# DumbCar.net
KiCad netlist of a schematic drawn in EAGLE
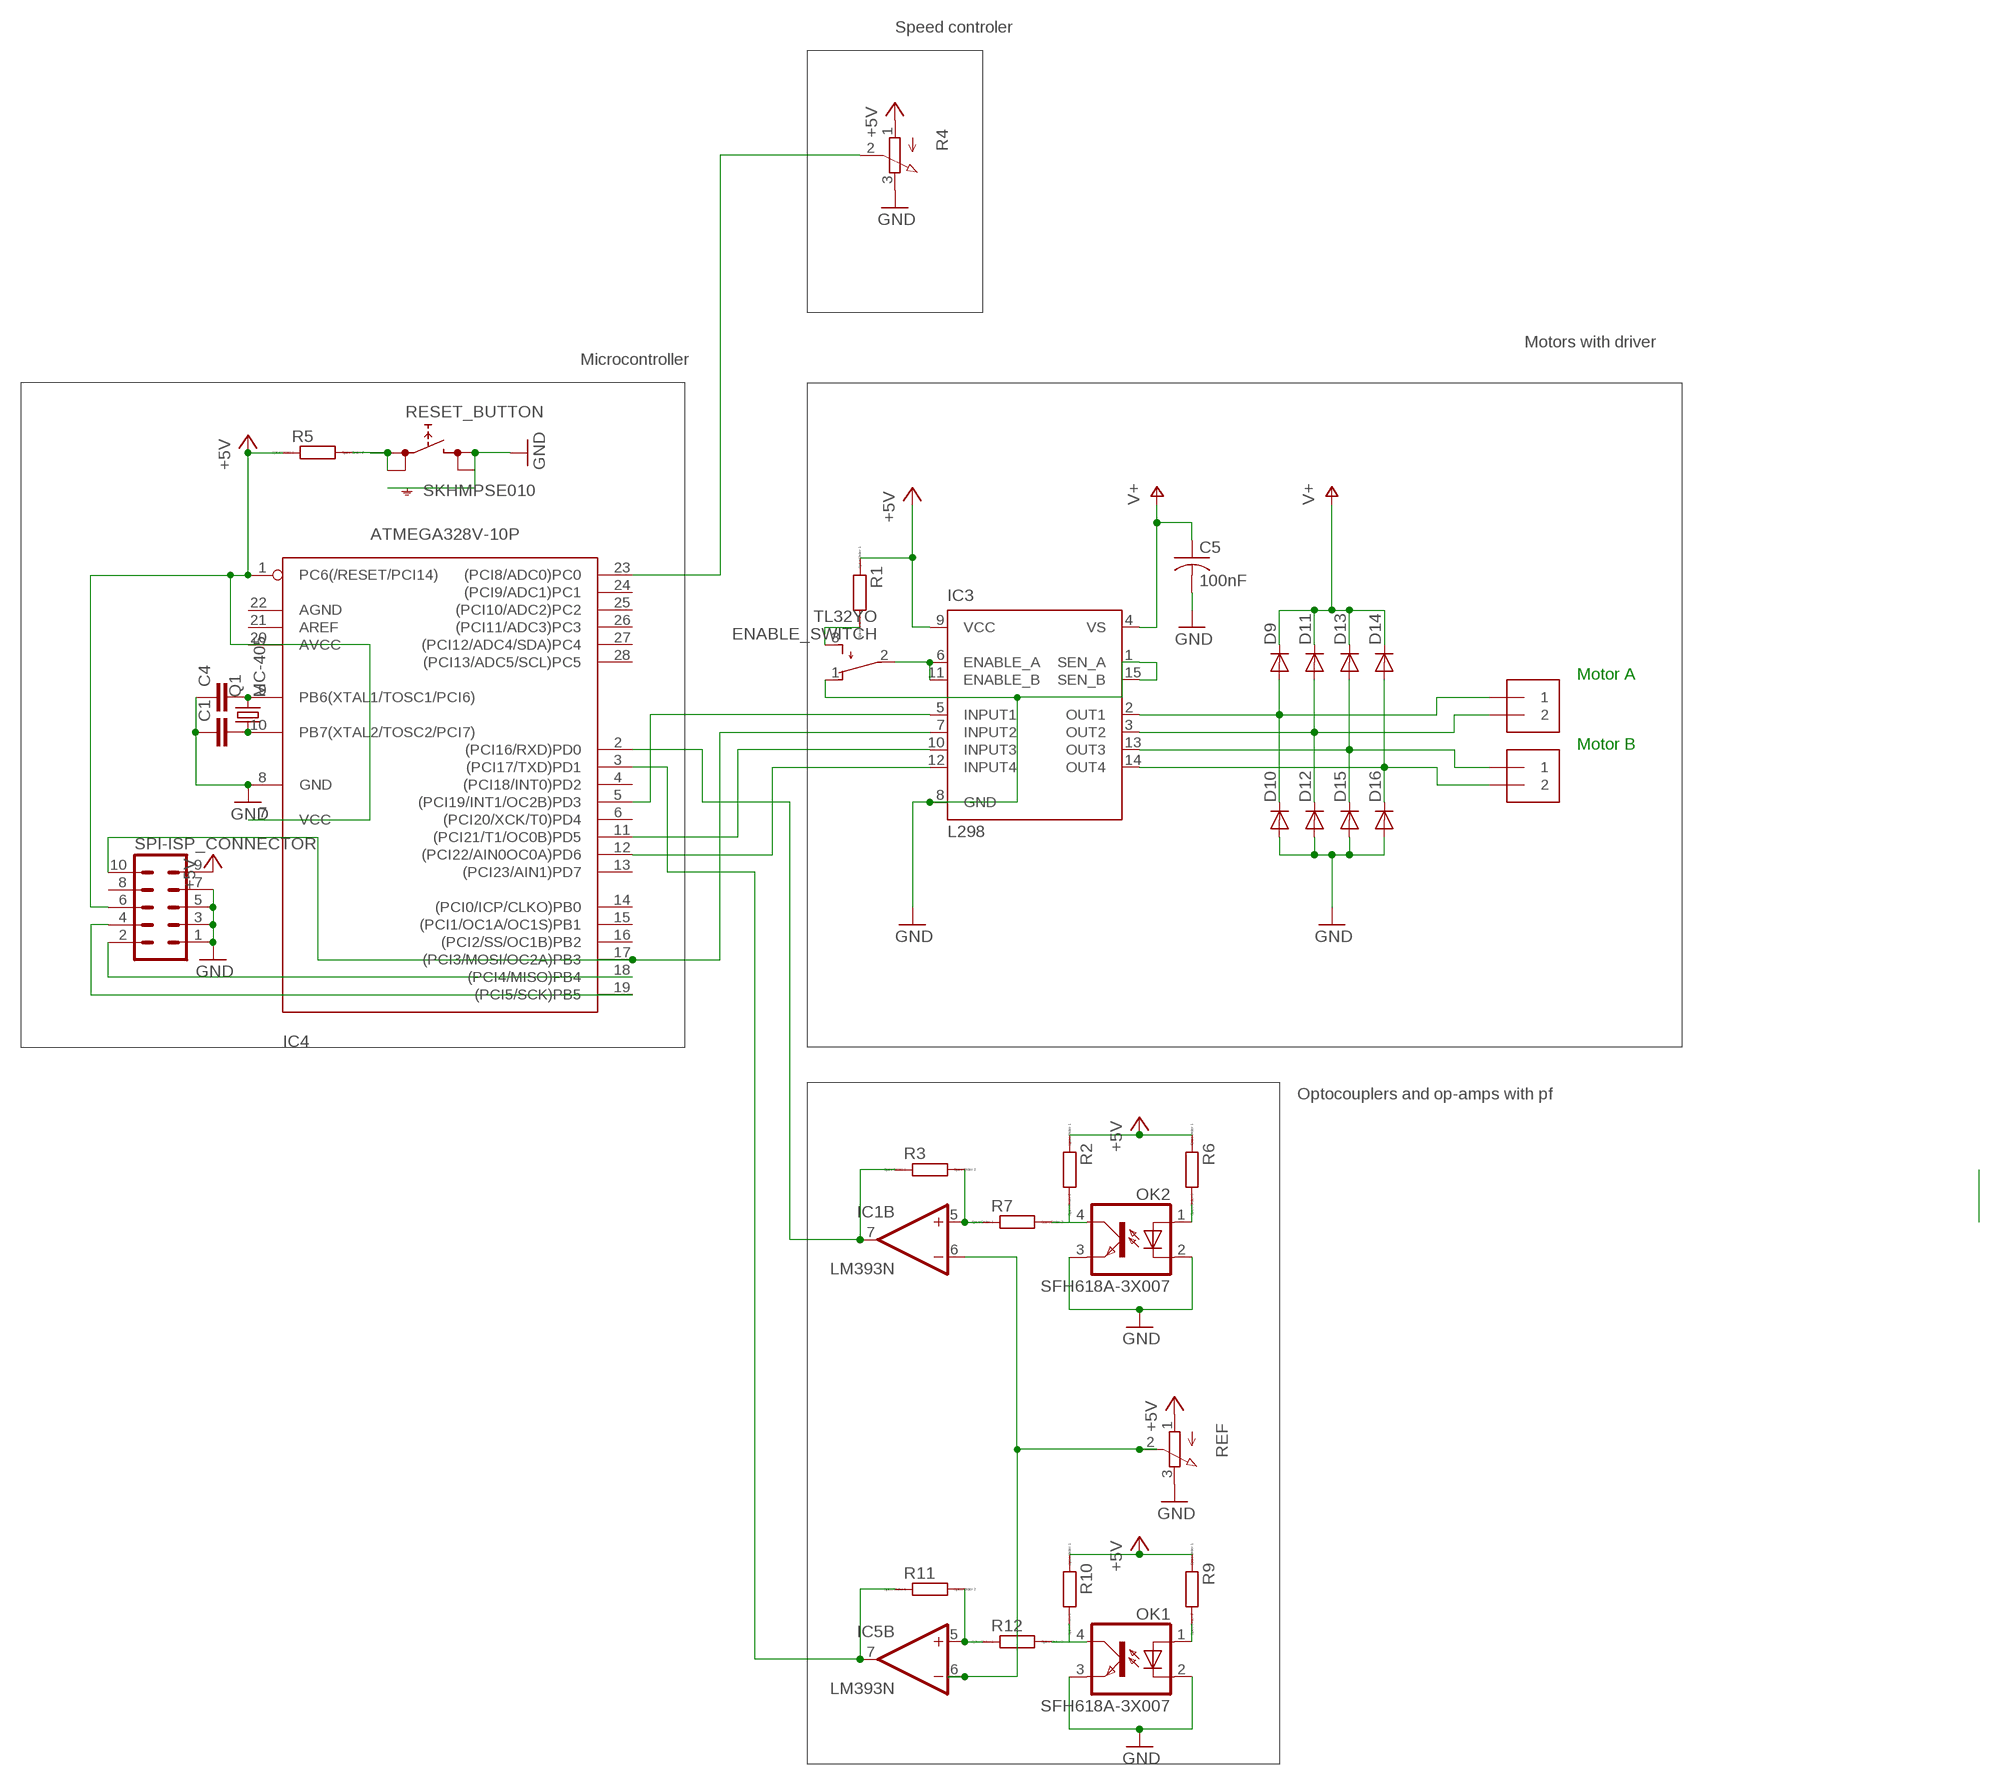
[diagram p0: schematic, sheet 1]
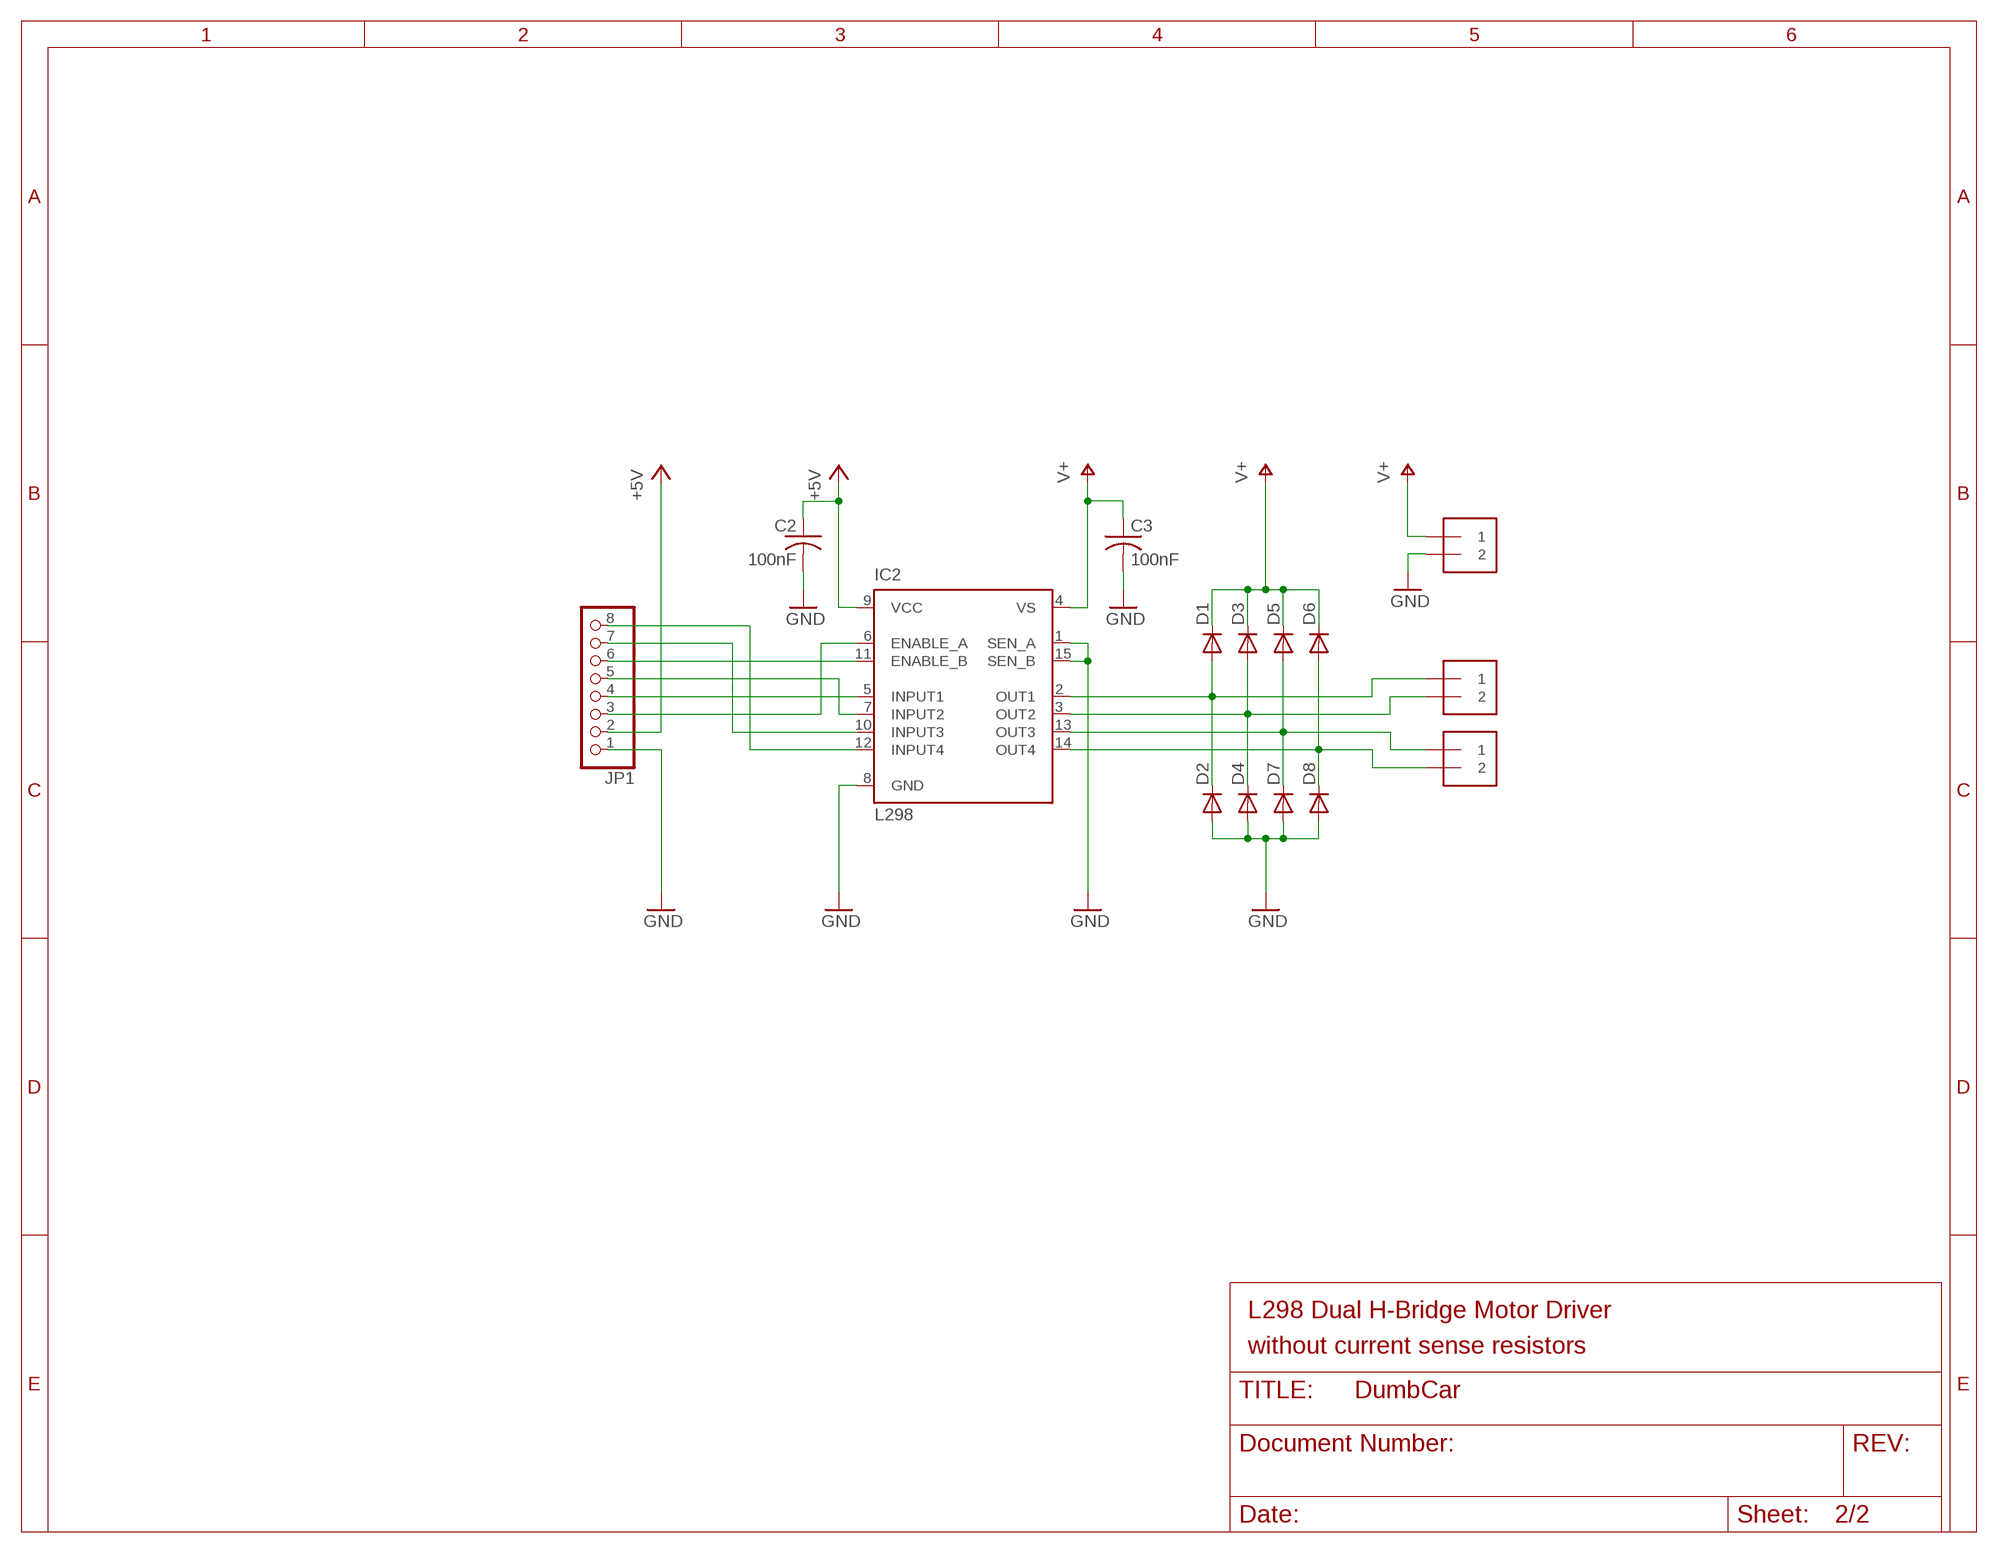
[diagram p1: schematic, sheet 2]

(export (version "E")
  (design (tool "Eeschema 10.0.6"))
  (components
    (comp (ref "C1")
      (value "C2.5/5")
      (footprint "eagle-import:C2.5-5")
      (libsource (lib "eagle-import") (part "C2.5/5"))
    )
    (comp (ref "C4")
      (value "C2.5/5")
      (footprint "eagle-import:C2.5-5")
      (libsource (lib "eagle-import") (part "C2.5/5"))
    )
    (comp (ref "C5")
      (value "100nF")
      (footprint "eagle-import:C050-024X044")
      (libsource (lib "eagle-import") (part "C-US050-024X044"))
    )
    (comp (ref "D9")
      (value "DIODE-D-5")
      (footprint "eagle-import:D-5")
      (libsource (lib "eagle-import") (part "DIODE-D-5"))
    )
    (comp (ref "D10")
      (value "DIODE-D-5")
      (footprint "eagle-import:D-5")
      (libsource (lib "eagle-import") (part "DIODE-D-5"))
    )
    (comp (ref "D11")
      (value "DIODE-D-5")
      (footprint "eagle-import:D-5")
      (libsource (lib "eagle-import") (part "DIODE-D-5"))
    )
    (comp (ref "D12")
      (value "DIODE-D-5")
      (footprint "eagle-import:D-5")
      (libsource (lib "eagle-import") (part "DIODE-D-5"))
    )
    (comp (ref "D13")
      (value "DIODE-D-5")
      (footprint "eagle-import:D-5")
      (libsource (lib "eagle-import") (part "DIODE-D-5"))
    )
    (comp (ref "D14")
      (value "DIODE-D-5")
      (footprint "eagle-import:D-5")
      (libsource (lib "eagle-import") (part "DIODE-D-5"))
    )
    (comp (ref "D15")
      (value "DIODE-D-5")
      (footprint "eagle-import:D-5")
      (libsource (lib "eagle-import") (part "DIODE-D-5"))
    )
    (comp (ref "D16")
      (value "DIODE-D-5")
      (footprint "eagle-import:D-5")
      (libsource (lib "eagle-import") (part "DIODE-D-5"))
    )
    (comp (ref "ENABLE_SWITCH")
      (value "TL32YO")
      (footprint "eagle-import:TL3XYO")
      (libsource (lib "eagle-import") (part "TL32YO"))
    )
    (comp (ref "IC1")
      (value "LM393N")
      (footprint "eagle-import:DIL08")
      (libsource (lib "eagle-import") (part "LM393N"))
    )
    (comp (ref "IC3")
      (value "L298")
      (footprint "eagle-import:MULTIWATT-15")
      (fields (field (name "MPN") "L298N"))
      (libsource (lib "eagle-import") (part "L298"))
    )
    (comp (ref "IC4")
      (value "ATMEGA328V-10P")
      (footprint "eagle-import:DIL28-3")
      (libsource (lib "eagle-import") (part "ATMEGA328PV-10"))
    )
    (comp (ref "IC5")
      (value "LM393N")
      (footprint "eagle-import:DIL08")
      (libsource (lib "eagle-import") (part "LM393N"))
    )
    (comp (ref "J6")
      (value "1X2-3.5MM")
      (footprint "eagle-import:1X2-3.5MM")
      (libsource (lib "eagle-import") (part "1X2-3.5MM"))
    )
    (comp (ref "J7")
      (value "1X2-3.5MM")
      (footprint "eagle-import:1X2-3.5MM")
      (libsource (lib "eagle-import") (part "1X2-3.5MM"))
    )
    (comp (ref "OK1")
      (value "SFH618A-3X007")
      (footprint "eagle-import:SMD4-7")
      (libsource (lib "eagle-import") (part "SFH618?A-3X007"))
    )
    (comp (ref "OK2")
      (value "SFH618A-3X007")
      (footprint "eagle-import:SMD4-7")
      (libsource (lib "eagle-import") (part "SFH618?A-3X007"))
    )
    (comp (ref "Q1")
      (value "MC-405")
      (footprint "eagle-import:MC-405")
      (libsource (lib "eagle-import") (part "MC-405"))
    )
    (comp (ref "R1")
      (value "R0204/7")
      (footprint "eagle-import:0204_7")
      (libsource (lib "eagle-import") (part "R0204/7"))
    )
    (comp (ref "R2")
      (value "R0204/7")
      (footprint "eagle-import:0204_7")
      (libsource (lib "eagle-import") (part "R0204/7"))
    )
    (comp (ref "R3")
      (value "R0204/7")
      (footprint "eagle-import:0204_7")
      (libsource (lib "eagle-import") (part "R0204/7"))
    )
    (comp (ref "R4")
      (value "3RP/1610N")
      (footprint "eagle-import:3RP_1610N")
      (libsource (lib "eagle-import") (part "3RP/1610N"))
    )
    (comp (ref "R5")
      (value "R0204/7")
      (footprint "eagle-import:0204_7")
      (libsource (lib "eagle-import") (part "R0204/7"))
    )
    (comp (ref "R6")
      (value "R0204/7")
      (footprint "eagle-import:0204_7")
      (libsource (lib "eagle-import") (part "R0204/7"))
    )
    (comp (ref "R7")
      (value "R0204/7")
      (footprint "eagle-import:0204_7")
      (libsource (lib "eagle-import") (part "R0204/7"))
    )
    (comp (ref "R9")
      (value "R0204/7")
      (footprint "eagle-import:0204_7")
      (libsource (lib "eagle-import") (part "R0204/7"))
    )
    (comp (ref "R10")
      (value "R0204/7")
      (footprint "eagle-import:0204_7")
      (libsource (lib "eagle-import") (part "R0204/7"))
    )
    (comp (ref "R11")
      (value "R0204/7")
      (footprint "eagle-import:0204_7")
      (libsource (lib "eagle-import") (part "R0204/7"))
    )
    (comp (ref "R12")
      (value "R0204/7")
      (footprint "eagle-import:0204_7")
      (libsource (lib "eagle-import") (part "R0204/7"))
    )
    (comp (ref "REF")
      (value "3RP/1610N")
      (footprint "eagle-import:3RP_1610N")
      (libsource (lib "eagle-import") (part "3RP/1610N"))
    )
    (comp (ref "RESET_BUTTON")
      (value "SKHMPSE010")
      (footprint "eagle-import:SKHMPXE010")
      (libsource (lib "eagle-import") (part "SKHMPE010S"))
    )
    (comp (ref "SPI-ISP_CONNECTOR")
      (value "MA05-2")
      (footprint "eagle-import:MA05-2")
      (libsource (lib "eagle-import") (part "MA05-2"))
    )
    (comp (ref "C2")
      (value "100nF")
      (footprint "eagle-import:C050-024X044")
      (libsource (lib "eagle-import") (part "C-US050-024X044"))
    )
    (comp (ref "C3")
      (value "100nF")
      (footprint "eagle-import:C050-024X044")
      (libsource (lib "eagle-import") (part "C-US050-024X044"))
    )
    (comp (ref "D1")
      (value "DIODE-D-5")
      (footprint "eagle-import:D-5")
      (libsource (lib "eagle-import") (part "DIODE-D-5"))
    )
    (comp (ref "D2")
      (value "DIODE-D-5")
      (footprint "eagle-import:D-5")
      (libsource (lib "eagle-import") (part "DIODE-D-5"))
    )
    (comp (ref "D3")
      (value "DIODE-D-5")
      (footprint "eagle-import:D-5")
      (libsource (lib "eagle-import") (part "DIODE-D-5"))
    )
    (comp (ref "D4")
      (value "DIODE-D-5")
      (footprint "eagle-import:D-5")
      (libsource (lib "eagle-import") (part "DIODE-D-5"))
    )
    (comp (ref "D5")
      (value "DIODE-D-5")
      (footprint "eagle-import:D-5")
      (libsource (lib "eagle-import") (part "DIODE-D-5"))
    )
    (comp (ref "D6")
      (value "DIODE-D-5")
      (footprint "eagle-import:D-5")
      (libsource (lib "eagle-import") (part "DIODE-D-5"))
    )
    (comp (ref "D7")
      (value "DIODE-D-5")
      (footprint "eagle-import:D-5")
      (libsource (lib "eagle-import") (part "DIODE-D-5"))
    )
    (comp (ref "D8")
      (value "DIODE-D-5")
      (footprint "eagle-import:D-5")
      (libsource (lib "eagle-import") (part "DIODE-D-5"))
    )
    (comp (ref "IC2")
      (value "L298")
      (footprint "eagle-import:MULTIWATT-15")
      (fields (field (name "MPN") "L298N"))
      (libsource (lib "eagle-import") (part "L298"))
    )
    (comp (ref "J2")
      (value "1X2-3.5MM")
      (footprint "eagle-import:1X2-3.5MM")
      (libsource (lib "eagle-import") (part "1X2-3.5MM"))
    )
    (comp (ref "J3")
      (value "1X2-3.5MM")
      (footprint "eagle-import:1X2-3.5MM")
      (libsource (lib "eagle-import") (part "1X2-3.5MM"))
    )
    (comp (ref "J4")
      (value "1X2-3.5MM")
      (footprint "eagle-import:1X2-3.5MM")
      (libsource (lib "eagle-import") (part "1X2-3.5MM"))
    )
    (comp (ref "JP1")
      (value "PINHD-1X8")
      (footprint "eagle-import:1X08")
      (libsource (lib "eagle-import") (part "PINHD-1X8"))
    )
  )
  (nets
    (net (code "1") (name "+5V") (class "Default")
      (node (ref "C2") (pin "1") (pinfunction "1_1") (pintype "passive"))
      (node (ref "IC2") (pin "9") (pinfunction "VCC_9") (pintype "power_in"))
      (node (ref "IC3") (pin "9") (pinfunction "VCC_9") (pintype "power_in"))
      (node (ref "IC4") (pin "1") (pinfunction "PC6(/RESET/PCI14)_1") (pintype "bidirectional"))
      (node (ref "IC4") (pin "20") (pinfunction "AVCC_20") (pintype "bidirectional"))
      (node (ref "IC4") (pin "7") (pinfunction "VCC_7") (pintype "bidirectional"))
      (node (ref "JP1") (pin "2") (pinfunction "2_2") (pintype "passive"))
      (node (ref "R1") (pin "1") (pinfunction "1_1") (pintype "passive"))
      (node (ref "R10") (pin "1") (pinfunction "1_1") (pintype "passive"))
      (node (ref "R2") (pin "1") (pinfunction "1_1") (pintype "passive"))
      (node (ref "R4") (pin "1") (pinfunction "A_1") (pintype "passive"))
      (node (ref "R5") (pin "1") (pinfunction "1_1") (pintype "passive"))
      (node (ref "R6") (pin "1") (pinfunction "1_1") (pintype "passive"))
      (node (ref "R9") (pin "1") (pinfunction "1_1") (pintype "passive"))
      (node (ref "REF") (pin "1") (pinfunction "A_1") (pintype "passive"))
      (node (ref "SPI-ISP_CONNECTOR") (pin "6") (pinfunction "6_6") (pintype "passive"))
      (node (ref "SPI-ISP_CONNECTOR") (pin "9") (pinfunction "9_9") (pintype "passive"))
    )
    (net (code "2") (name "GND") (class "Default")
      (node (ref "C1") (pin "1") (pinfunction "1_1") (pintype "passive"))
      (node (ref "C2") (pin "2") (pinfunction "2_2") (pintype "passive"))
      (node (ref "C3") (pin "2") (pinfunction "2_2") (pintype "passive"))
      (node (ref "C4") (pin "1") (pinfunction "1_1") (pintype "passive"))
      (node (ref "C5") (pin "2") (pinfunction "2_2") (pintype "passive"))
      (node (ref "D10") (pin "A") (pinfunction "A_A") (pintype "passive"))
      (node (ref "D12") (pin "A") (pinfunction "A_A") (pintype "passive"))
      (node (ref "D15") (pin "A") (pinfunction "A_A") (pintype "passive"))
      (node (ref "D16") (pin "A") (pinfunction "A_A") (pintype "passive"))
      (node (ref "D2") (pin "A") (pinfunction "A_A") (pintype "passive"))
      (node (ref "D4") (pin "A") (pinfunction "A_A") (pintype "passive"))
      (node (ref "D7") (pin "A") (pinfunction "A_A") (pintype "passive"))
      (node (ref "D8") (pin "A") (pinfunction "A_A") (pintype "passive"))
      (node (ref "ENABLE_SWITCH") (pin "1") (pinfunction "O_1") (pintype "passive"))
      (node (ref "IC2") (pin "1") (pinfunction "SEN_A_1") (pintype "input"))
      (node (ref "IC2") (pin "15") (pinfunction "SEN_B_15") (pintype "input"))
      (node (ref "IC2") (pin "8") (pinfunction "GND_8") (pintype "power_in"))
      (node (ref "IC3") (pin "1") (pinfunction "SEN_A_1") (pintype "input"))
      (node (ref "IC3") (pin "15") (pinfunction "SEN_B_15") (pintype "input"))
      (node (ref "IC3") (pin "8") (pinfunction "GND_8") (pintype "power_in"))
      (node (ref "IC4") (pin "8") (pinfunction "GND_8") (pintype "bidirectional"))
      (node (ref "J2") (pin "2") (pinfunction "2_2") (pintype "passive"))
      (node (ref "JP1") (pin "1") (pinfunction "1_1") (pintype "passive"))
      (node (ref "OK1") (pin "2") (pinfunction "C_2") (pintype "passive"))
      (node (ref "OK1") (pin "3") (pinfunction "EMIT_3") (pintype "passive"))
      (node (ref "OK2") (pin "2") (pinfunction "C_2") (pintype "passive"))
      (node (ref "OK2") (pin "3") (pinfunction "EMIT_3") (pintype "passive"))
      (node (ref "R4") (pin "3") (pinfunction "E_3") (pintype "passive"))
      (node (ref "REF") (pin "3") (pinfunction "E_3") (pintype "passive"))
      (node (ref "RESET_BUTTON") (pin "3") (pinfunction "2.1_3") (pintype "passive"))
      (node (ref "RESET_BUTTON") (pin "4") (pinfunction "2.2_4") (pintype "passive"))
      (node (ref "RESET_BUTTON") (pin "5") (pinfunction "SH_5") (pintype "passive"))
      (node (ref "SPI-ISP_CONNECTOR") (pin "1") (pinfunction "1_1") (pintype "passive"))
      (node (ref "SPI-ISP_CONNECTOR") (pin "3") (pinfunction "3_3") (pintype "passive"))
      (node (ref "SPI-ISP_CONNECTOR") (pin "5") (pinfunction "5_5") (pintype "passive"))
      (node (ref "SPI-ISP_CONNECTOR") (pin "7") (pinfunction "7_7") (pintype "passive"))
    )
    (net (code "3") (name "Net-(ENABLE_SWITCH-P)") (class "Default")
      (node (ref "ENABLE_SWITCH") (pin "2") (pinfunction "P_2") (pintype "passive"))
      (node (ref "IC3") (pin "11") (pinfunction "ENABLE_B_11") (pintype "input"))
      (node (ref "IC3") (pin "6") (pinfunction "ENABLE_A_6") (pintype "input"))
    )
    (net (code "4") (name "Net-(ENABLE_SWITCH-S)") (class "Default")
      (node (ref "ENABLE_SWITCH") (pin "3") (pinfunction "S_3") (pintype "passive"))
      (node (ref "R1") (pin "2") (pinfunction "2_2") (pintype "passive"))
    )
    (net (code "5") (name "Net-(IC1B-+IN)") (class "Default")
      (node (ref "IC1") (pin "5") (pinfunction "+IN_5") (pintype "input"))
      (node (ref "R3") (pin "2") (pinfunction "2_2") (pintype "passive"))
      (node (ref "R7") (pin "1") (pinfunction "1_1") (pintype "passive"))
    )
    (net (code "6") (name "Net-(IC1B--IN)") (class "Default")
      (node (ref "IC1") (pin "6") (pinfunction "-IN_6") (pintype "input"))
      (node (ref "IC5") (pin "6") (pinfunction "-IN_6") (pintype "input"))
      (node (ref "REF") (pin "2") (pinfunction "S_2") (pintype "passive"))
    )
    (net (code "7") (name "Net-(IC1B-OUT)") (class "Default")
      (node (ref "IC1") (pin "7") (pinfunction "OUT_7") (pintype "output"))
      (node (ref "IC4") (pin "2") (pinfunction "(PCI16/RXD)PD0_2") (pintype "bidirectional"))
      (node (ref "R3") (pin "1") (pinfunction "1_1") (pintype "passive"))
    )
    (net (code "8") (name "Net-(IC2-ENABLE_A)") (class "Default")
      (node (ref "IC2") (pin "6") (pinfunction "ENABLE_A_6") (pintype "input"))
      (node (ref "JP1") (pin "3") (pinfunction "3_3") (pintype "passive"))
    )
    (net (code "9") (name "Net-(IC2-ENABLE_B)") (class "Default")
      (node (ref "IC2") (pin "11") (pinfunction "ENABLE_B_11") (pintype "input"))
      (node (ref "JP1") (pin "6") (pinfunction "6_6") (pintype "passive"))
    )
    (net (code "10") (name "Net-(IC2-INPUT1)") (class "Default")
      (node (ref "IC2") (pin "5") (pinfunction "INPUT1_5") (pintype "input"))
      (node (ref "JP1") (pin "4") (pinfunction "4_4") (pintype "passive"))
    )
    (net (code "11") (name "Net-(IC2-INPUT2)") (class "Default")
      (node (ref "IC2") (pin "7") (pinfunction "INPUT2_7") (pintype "input"))
      (node (ref "JP1") (pin "5") (pinfunction "5_5") (pintype "passive"))
    )
    (net (code "12") (name "Net-(IC2-INPUT3)") (class "Default")
      (node (ref "IC2") (pin "10") (pinfunction "INPUT3_10") (pintype "input"))
      (node (ref "JP1") (pin "7") (pinfunction "7_7") (pintype "passive"))
    )
    (net (code "13") (name "Net-(IC2-INPUT4)") (class "Default")
      (node (ref "IC2") (pin "12") (pinfunction "INPUT4_12") (pintype "input"))
      (node (ref "JP1") (pin "8") (pinfunction "8_8") (pintype "passive"))
    )
    (net (code "14") (name "Net-(IC2-OUT1)") (class "Default")
      (node (ref "D1") (pin "A") (pinfunction "A_A") (pintype "passive"))
      (node (ref "D2") (pin "C") (pinfunction "C_C") (pintype "passive"))
      (node (ref "IC2") (pin "2") (pinfunction "OUT1_2") (pintype "output"))
      (node (ref "J3") (pin "1") (pinfunction "1_1") (pintype "passive"))
    )
    (net (code "15") (name "Net-(IC2-OUT2)") (class "Default")
      (node (ref "D3") (pin "A") (pinfunction "A_A") (pintype "passive"))
      (node (ref "D4") (pin "C") (pinfunction "C_C") (pintype "passive"))
      (node (ref "IC2") (pin "3") (pinfunction "OUT2_3") (pintype "output"))
      (node (ref "J3") (pin "2") (pinfunction "2_2") (pintype "passive"))
    )
    (net (code "16") (name "Net-(IC2-OUT3)") (class "Default")
      (node (ref "D5") (pin "A") (pinfunction "A_A") (pintype "passive"))
      (node (ref "D7") (pin "C") (pinfunction "C_C") (pintype "passive"))
      (node (ref "IC2") (pin "13") (pinfunction "OUT3_13") (pintype "output"))
      (node (ref "J4") (pin "1") (pinfunction "1_1") (pintype "passive"))
    )
    (net (code "17") (name "Net-(IC2-OUT4)") (class "Default")
      (node (ref "D6") (pin "A") (pinfunction "A_A") (pintype "passive"))
      (node (ref "D8") (pin "C") (pinfunction "C_C") (pintype "passive"))
      (node (ref "IC2") (pin "14") (pinfunction "OUT4_14") (pintype "output"))
      (node (ref "J4") (pin "2") (pinfunction "2_2") (pintype "passive"))
    )
    (net (code "18") (name "Net-(IC3-INPUT1)") (class "Default")
      (node (ref "IC3") (pin "5") (pinfunction "INPUT1_5") (pintype "input"))
      (node (ref "IC4") (pin "5") (pinfunction "(PCI19/INT1/OC2B)PD3_5") (pintype "bidirectional"))
    )
    (net (code "19") (name "Net-(IC3-INPUT2)") (class "Default")
      (node (ref "IC3") (pin "7") (pinfunction "INPUT2_7") (pintype "input"))
      (node (ref "IC4") (pin "17") (pinfunction "(PCI3/MOSI/OC2A)PB3_17") (pintype "bidirectional"))
      (node (ref "SPI-ISP_CONNECTOR") (pin "10") (pinfunction "10_10") (pintype "passive"))
    )
    (net (code "20") (name "Net-(IC3-INPUT3)") (class "Default")
      (node (ref "IC3") (pin "10") (pinfunction "INPUT3_10") (pintype "input"))
      (node (ref "IC4") (pin "11") (pinfunction "(PCI21/T1/OC0B)PD5_11") (pintype "bidirectional"))
    )
    (net (code "21") (name "Net-(IC3-INPUT4)") (class "Default")
      (node (ref "IC3") (pin "12") (pinfunction "INPUT4_12") (pintype "input"))
      (node (ref "IC4") (pin "12") (pinfunction "(PCI22/AIN0OC0A)PD6_12") (pintype "bidirectional"))
    )
    (net (code "22") (name "Net-(IC3-OUT1)") (class "Default")
      (node (ref "D10") (pin "C") (pinfunction "C_C") (pintype "passive"))
      (node (ref "D9") (pin "A") (pinfunction "A_A") (pintype "passive"))
      (node (ref "IC3") (pin "2") (pinfunction "OUT1_2") (pintype "output"))
      (node (ref "J6") (pin "1") (pinfunction "1_1") (pintype "passive"))
    )
    (net (code "23") (name "Net-(IC3-OUT2)") (class "Default")
      (node (ref "D11") (pin "A") (pinfunction "A_A") (pintype "passive"))
      (node (ref "D12") (pin "C") (pinfunction "C_C") (pintype "passive"))
      (node (ref "IC3") (pin "3") (pinfunction "OUT2_3") (pintype "output"))
      (node (ref "J6") (pin "2") (pinfunction "2_2") (pintype "passive"))
    )
    (net (code "24") (name "Net-(IC3-OUT3)") (class "Default")
      (node (ref "D13") (pin "A") (pinfunction "A_A") (pintype "passive"))
      (node (ref "D15") (pin "C") (pinfunction "C_C") (pintype "passive"))
      (node (ref "IC3") (pin "13") (pinfunction "OUT3_13") (pintype "output"))
      (node (ref "J7") (pin "1") (pinfunction "1_1") (pintype "passive"))
    )
    (net (code "25") (name "Net-(IC3-OUT4)") (class "Default")
      (node (ref "D14") (pin "A") (pinfunction "A_A") (pintype "passive"))
      (node (ref "D16") (pin "C") (pinfunction "C_C") (pintype "passive"))
      (node (ref "IC3") (pin "14") (pinfunction "OUT4_14") (pintype "output"))
      (node (ref "J7") (pin "2") (pinfunction "2_2") (pintype "passive"))
    )
    (net (code "26") (name "Net-(IC4-(PCI4{slash}MISO)PB4)") (class "Default")
      (node (ref "IC4") (pin "18") (pinfunction "(PCI4/MISO)PB4_18") (pintype "bidirectional"))
      (node (ref "SPI-ISP_CONNECTOR") (pin "2") (pinfunction "2_2") (pintype "passive"))
    )
    (net (code "27") (name "Net-(IC4-(PCI5{slash}SCK)PB5)") (class "Default")
      (node (ref "IC4") (pin "19") (pinfunction "(PCI5/SCK)PB5_19") (pintype "bidirectional"))
      (node (ref "SPI-ISP_CONNECTOR") (pin "4") (pinfunction "4_4") (pintype "passive"))
    )
    (net (code "28") (name "Net-(IC4-(PCI8{slash}ADC0)PC0)") (class "Default")
      (node (ref "IC4") (pin "23") (pinfunction "(PCI8/ADC0)PC0_23") (pintype "bidirectional"))
      (node (ref "R4") (pin "2") (pinfunction "S_2") (pintype "passive"))
    )
    (net (code "29") (name "Net-(IC4-(PCI17{slash}TXD)PD1)") (class "Default")
      (node (ref "IC4") (pin "3") (pinfunction "(PCI17/TXD)PD1_3") (pintype "bidirectional"))
      (node (ref "IC5") (pin "7") (pinfunction "OUT_7") (pintype "output"))
      (node (ref "R11") (pin "1") (pinfunction "1_1") (pintype "passive"))
    )
    (net (code "30") (name "Net-(IC4-PB6(XTAL1{slash}TOSC1{slash}PCI6))") (class "Default")
      (node (ref "C4") (pin "2") (pinfunction "2_2") (pintype "passive"))
      (node (ref "IC4") (pin "9") (pinfunction "PB6(XTAL1/TOSC1/PCI6)_9") (pintype "bidirectional"))
      (node (ref "Q1") (pin "2") (pinfunction "2_2") (pintype "passive"))
    )
    (net (code "31") (name "Net-(IC4-PB7(XTAL2{slash}TOSC2{slash}PCI7))") (class "Default")
      (node (ref "C1") (pin "2") (pinfunction "2_2") (pintype "passive"))
      (node (ref "IC4") (pin "10") (pinfunction "PB7(XTAL2/TOSC2/PCI7)_10") (pintype "bidirectional"))
      (node (ref "Q1") (pin "1") (pinfunction "1_1") (pintype "passive"))
    )
    (net (code "32") (name "Net-(IC5B-+IN)") (class "Default")
      (node (ref "IC5") (pin "5") (pinfunction "+IN_5") (pintype "input"))
      (node (ref "R11") (pin "2") (pinfunction "2_2") (pintype "passive"))
      (node (ref "R12") (pin "1") (pinfunction "1_1") (pintype "passive"))
    )
    (net (code "33") (name "Net-(OK1-A)") (class "Default")
      (node (ref "OK1") (pin "1") (pinfunction "A_1") (pintype "passive"))
      (node (ref "R9") (pin "2") (pinfunction "2_2") (pintype "passive"))
    )
    (net (code "34") (name "Net-(OK1-COL)") (class "Default")
      (node (ref "OK1") (pin "4") (pinfunction "COL_4") (pintype "passive"))
      (node (ref "R10") (pin "2") (pinfunction "2_2") (pintype "passive"))
    )
    (net (code "35") (name "Net-(OK2-A)") (class "Default")
      (node (ref "OK2") (pin "1") (pinfunction "A_1") (pintype "passive"))
      (node (ref "R6") (pin "2") (pinfunction "2_2") (pintype "passive"))
    )
    (net (code "36") (name "Net-(OK2-COL)") (class "Default")
      (node (ref "OK2") (pin "4") (pinfunction "COL_4") (pintype "passive"))
      (node (ref "R2") (pin "2") (pinfunction "2_2") (pintype "passive"))
    )
    (net (code "37") (name "Net-(RESET_BUTTON-1.1)") (class "Default")
      (node (ref "R5") (pin "2") (pinfunction "2_2") (pintype "passive"))
      (node (ref "RESET_BUTTON") (pin "1") (pinfunction "1.1_1") (pintype "passive"))
      (node (ref "RESET_BUTTON") (pin "2") (pinfunction "1.2_2") (pintype "passive"))
    )
    (net (code "38") (name "V+") (class "Default")
      (node (ref "C3") (pin "1") (pinfunction "1_1") (pintype "passive"))
      (node (ref "C5") (pin "1") (pinfunction "1_1") (pintype "passive"))
      (node (ref "D1") (pin "C") (pinfunction "C_C") (pintype "passive"))
      (node (ref "D11") (pin "C") (pinfunction "C_C") (pintype "passive"))
      (node (ref "D13") (pin "C") (pinfunction "C_C") (pintype "passive"))
      (node (ref "D14") (pin "C") (pinfunction "C_C") (pintype "passive"))
      (node (ref "D3") (pin "C") (pinfunction "C_C") (pintype "passive"))
      (node (ref "D5") (pin "C") (pinfunction "C_C") (pintype "passive"))
      (node (ref "D6") (pin "C") (pinfunction "C_C") (pintype "passive"))
      (node (ref "D9") (pin "C") (pinfunction "C_C") (pintype "passive"))
      (node (ref "IC2") (pin "4") (pinfunction "VS_4") (pintype "power_in"))
      (node (ref "IC3") (pin "4") (pinfunction "VS_4") (pintype "power_in"))
      (node (ref "J2") (pin "1") (pinfunction "1_1") (pintype "passive"))
    )
    (net (code "39") (name "unconnected-(IC4-(PCI0{slash}ICP{slash}CLKO)PB0-Pad14)") (class "Default")
      (node (ref "IC4") (pin "14") (pinfunction "(PCI0/ICP/CLKO)PB0_14") (pintype "bidirectional"))
    )
    (net (code "40") (name "unconnected-(IC4-(PCI1{slash}OC1A{slash}OC1S)PB1-Pad15)") (class "Default")
      (node (ref "IC4") (pin "15") (pinfunction "(PCI1/OC1A/OC1S)PB1_15") (pintype "bidirectional"))
    )
    (net (code "41") (name "unconnected-(IC4-(PCI2{slash}SS{slash}OC1B)PB2-Pad16)") (class "Default")
      (node (ref "IC4") (pin "16") (pinfunction "(PCI2/SS/OC1B)PB2_16") (pintype "bidirectional"))
    )
    (net (code "42") (name "unconnected-(IC4-(PCI9{slash}ADC1)PC1-Pad24)") (class "Default")
      (node (ref "IC4") (pin "24") (pinfunction "(PCI9/ADC1)PC1_24") (pintype "bidirectional"))
    )
    (net (code "43") (name "unconnected-(IC4-(PCI10{slash}ADC2)PC2-Pad25)") (class "Default")
      (node (ref "IC4") (pin "25") (pinfunction "(PCI10/ADC2)PC2_25") (pintype "bidirectional"))
    )
    (net (code "44") (name "unconnected-(IC4-(PCI11{slash}ADC3)PC3-Pad26)") (class "Default")
      (node (ref "IC4") (pin "26") (pinfunction "(PCI11/ADC3)PC3_26") (pintype "bidirectional"))
    )
    (net (code "45") (name "unconnected-(IC4-(PCI12{slash}ADC4{slash}SDA)PC4-Pad27)") (class "Default")
      (node (ref "IC4") (pin "27") (pinfunction "(PCI12/ADC4/SDA)PC4_27") (pintype "bidirectional"))
    )
    (net (code "46") (name "unconnected-(IC4-(PCI13{slash}ADC5{slash}SCL)PC5-Pad28)") (class "Default")
      (node (ref "IC4") (pin "28") (pinfunction "(PCI13/ADC5/SCL)PC5_28") (pintype "bidirectional"))
    )
    (net (code "47") (name "unconnected-(IC4-(PCI18{slash}INT0)PD2-Pad4)") (class "Default")
      (node (ref "IC4") (pin "4") (pinfunction "(PCI18/INT0)PD2_4") (pintype "bidirectional"))
    )
    (net (code "48") (name "unconnected-(IC4-(PCI20{slash}XCK{slash}T0)PD4-Pad6)") (class "Default")
      (node (ref "IC4") (pin "6") (pinfunction "(PCI20/XCK/T0)PD4_6") (pintype "bidirectional"))
    )
    (net (code "49") (name "unconnected-(IC4-(PCI23{slash}AIN1)PD7-Pad13)") (class "Default")
      (node (ref "IC4") (pin "13") (pinfunction "(PCI23/AIN1)PD7_13") (pintype "bidirectional"))
    )
    (net (code "50") (name "unconnected-(IC4-AGND-Pad22)") (class "Default")
      (node (ref "IC4") (pin "22") (pinfunction "AGND_22") (pintype "bidirectional"))
    )
    (net (code "51") (name "unconnected-(IC4-AREF-Pad21)") (class "Default")
      (node (ref "IC4") (pin "21") (pinfunction "AREF_21") (pintype "bidirectional"))
    )
    (net (code "52") (name "unconnected-(R7-Pad2)") (class "Default")
      (node (ref "R7") (pin "2") (pinfunction "2_2") (pintype "passive"))
    )
    (net (code "53") (name "unconnected-(R12-Pad2)") (class "Default")
      (node (ref "R12") (pin "2") (pinfunction "2_2") (pintype "passive"))
    )
    (net (code "54") (name "unconnected-(SPI-ISP_CONNECTOR-Pad8)") (class "Default")
      (node (ref "SPI-ISP_CONNECTOR") (pin "8") (pinfunction "8_8") (pintype "passive"))
    )
  )
)
